# io2db9.net
KiCad netlist of a schematic drawn in EAGLE
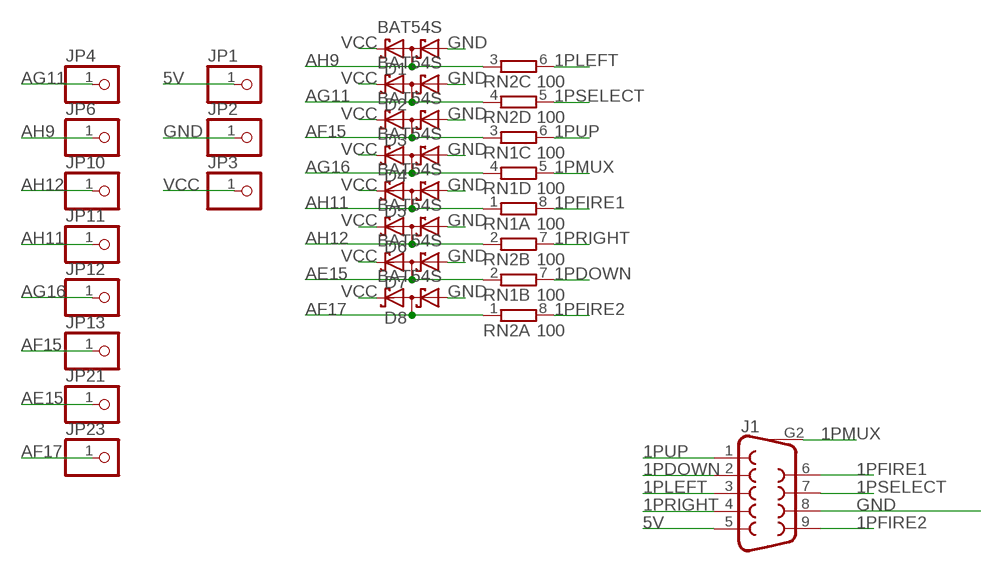
[diagram p0: schematic, sheet 1]

(export (version "E")
  (design (tool "Eeschema 10.0.6"))
  (components
    (comp (ref "D1")
      (value "BAT54S")
      (footprint "eagle-import:SOT23")
      (libsource (lib "eagle-import") (part "BAT54S"))
    )
    (comp (ref "D2")
      (value "BAT54S")
      (footprint "eagle-import:SOT23")
      (libsource (lib "eagle-import") (part "BAT54S"))
    )
    (comp (ref "D3")
      (value "BAT54S")
      (footprint "eagle-import:SOT23")
      (libsource (lib "eagle-import") (part "BAT54S"))
    )
    (comp (ref "D4")
      (value "BAT54S")
      (footprint "eagle-import:SOT23")
      (libsource (lib "eagle-import") (part "BAT54S"))
    )
    (comp (ref "D5")
      (value "BAT54S")
      (footprint "eagle-import:SOT23")
      (libsource (lib "eagle-import") (part "BAT54S"))
    )
    (comp (ref "D6")
      (value "BAT54S")
      (footprint "eagle-import:SOT23")
      (libsource (lib "eagle-import") (part "BAT54S"))
    )
    (comp (ref "D7")
      (value "BAT54S")
      (footprint "eagle-import:SOT23")
      (libsource (lib "eagle-import") (part "BAT54S"))
    )
    (comp (ref "D8")
      (value "BAT54S")
      (footprint "eagle-import:SOT23")
      (libsource (lib "eagle-import") (part "BAT54S"))
    )
    (comp (ref "J1")
      (value "SPARKFUN-CONNECTORS_DB9MALE")
      (footprint "eagle-import:SPARKFUN-CONNECTORS_DB9_MALE")
      (libsource (lib "eagle-import") (part "SPARKFUN-CONNECTORS_DB9MALE"))
    )
    (comp (ref "JP1")
      (value "PINHD-1X1")
      (footprint "eagle-import:1X01")
      (libsource (lib "eagle-import") (part "PINHD-1X1"))
    )
    (comp (ref "JP2")
      (value "PINHD-1X1")
      (footprint "eagle-import:1X01")
      (libsource (lib "eagle-import") (part "PINHD-1X1"))
    )
    (comp (ref "JP3")
      (value "PINHD-1X1")
      (footprint "eagle-import:1X01")
      (libsource (lib "eagle-import") (part "PINHD-1X1"))
    )
    (comp (ref "JP4")
      (value "PINHD-1X1")
      (footprint "eagle-import:1X01")
      (libsource (lib "eagle-import") (part "PINHD-1X1"))
    )
    (comp (ref "JP6")
      (value "PINHD-1X1")
      (footprint "eagle-import:1X01")
      (libsource (lib "eagle-import") (part "PINHD-1X1"))
    )
    (comp (ref "JP10")
      (value "PINHD-1X1")
      (footprint "eagle-import:1X01")
      (libsource (lib "eagle-import") (part "PINHD-1X1"))
    )
    (comp (ref "JP11")
      (value "PINHD-1X1")
      (footprint "eagle-import:1X01")
      (libsource (lib "eagle-import") (part "PINHD-1X1"))
    )
    (comp (ref "JP12")
      (value "PINHD-1X1")
      (footprint "eagle-import:1X01")
      (libsource (lib "eagle-import") (part "PINHD-1X1"))
    )
    (comp (ref "JP13")
      (value "PINHD-1X1")
      (footprint "eagle-import:1X01")
      (libsource (lib "eagle-import") (part "PINHD-1X1"))
    )
    (comp (ref "JP21")
      (value "PINHD-1X1")
      (footprint "eagle-import:1X01")
      (libsource (lib "eagle-import") (part "PINHD-1X1"))
    )
    (comp (ref "JP23")
      (value "PINHD-1X1")
      (footprint "eagle-import:1X01")
      (libsource (lib "eagle-import") (part "PINHD-1X1"))
    )
    (comp (ref "RN1")
      (value "100")
      (footprint "eagle-import:0603-ARC")
      (libsource (lib "eagle-import") (part "4R-N0603-ARC"))
    )
    (comp (ref "RN2")
      (value "100")
      (footprint "eagle-import:0603-ARC")
      (libsource (lib "eagle-import") (part "4R-N0603-ARC"))
    )
  )
  (nets
    (net (code "1") (name "/1PDOWN") (class "Default")
      (node (ref "J1") (pin "2") (pinfunction "2_2") (pintype "passive"))
      (node (ref "RN1") (pin "7") (pinfunction "2_7") (pintype "passive"))
    )
    (net (code "2") (name "/1PFIRE1") (class "Default")
      (node (ref "J1") (pin "6") (pinfunction "6_6") (pintype "passive"))
      (node (ref "RN1") (pin "8") (pinfunction "2_8") (pintype "passive"))
    )
    (net (code "3") (name "/1PFIRE2") (class "Default")
      (node (ref "J1") (pin "9") (pinfunction "9_9") (pintype "passive"))
      (node (ref "RN2") (pin "8") (pinfunction "2_8") (pintype "passive"))
    )
    (net (code "4") (name "/1PLEFT") (class "Default")
      (node (ref "J1") (pin "3") (pinfunction "3_3") (pintype "passive"))
      (node (ref "RN2") (pin "6") (pinfunction "2_6") (pintype "passive"))
    )
    (net (code "5") (name "/1PMUX") (class "Default")
      (node (ref "J1") (pin "G2") (pinfunction "10_G2") (pintype "passive"))
      (node (ref "RN1") (pin "5") (pinfunction "2_5") (pintype "passive"))
    )
    (net (code "6") (name "/1PRIGHT") (class "Default")
      (node (ref "J1") (pin "4") (pinfunction "4_4") (pintype "passive"))
      (node (ref "RN2") (pin "7") (pinfunction "2_7") (pintype "passive"))
    )
    (net (code "7") (name "/1PSELECT") (class "Default")
      (node (ref "J1") (pin "7") (pinfunction "7_7") (pintype "passive"))
      (node (ref "RN2") (pin "5") (pinfunction "2_5") (pintype "passive"))
    )
    (net (code "8") (name "/1PUP") (class "Default")
      (node (ref "J1") (pin "1") (pinfunction "1_1") (pintype "passive"))
      (node (ref "RN1") (pin "6") (pinfunction "2_6") (pintype "passive"))
    )
    (net (code "9") (name "/5V") (class "Default")
      (node (ref "J1") (pin "5") (pinfunction "5_5") (pintype "passive"))
      (node (ref "JP1") (pin "1") (pinfunction "1_1") (pintype "passive"))
    )
    (net (code "10") (name "/AE15") (class "Default")
      (node (ref "D7") (pin "3") (pinfunction "C1A2_3") (pintype "passive"))
      (node (ref "JP21") (pin "1") (pinfunction "1_1") (pintype "passive"))
      (node (ref "RN1") (pin "2") (pinfunction "1_2") (pintype "passive"))
    )
    (net (code "11") (name "/AF15") (class "Default")
      (node (ref "D3") (pin "3") (pinfunction "C1A2_3") (pintype "passive"))
      (node (ref "JP13") (pin "1") (pinfunction "1_1") (pintype "passive"))
      (node (ref "RN1") (pin "3") (pinfunction "1_3") (pintype "passive"))
    )
    (net (code "12") (name "/AF17") (class "Default")
      (node (ref "D8") (pin "3") (pinfunction "C1A2_3") (pintype "passive"))
      (node (ref "JP23") (pin "1") (pinfunction "1_1") (pintype "passive"))
      (node (ref "RN2") (pin "1") (pinfunction "1_1") (pintype "passive"))
    )
    (net (code "13") (name "/AG11") (class "Default")
      (node (ref "D2") (pin "3") (pinfunction "C1A2_3") (pintype "passive"))
      (node (ref "JP4") (pin "1") (pinfunction "1_1") (pintype "passive"))
      (node (ref "RN2") (pin "4") (pinfunction "1_4") (pintype "passive"))
    )
    (net (code "14") (name "/AG16") (class "Default")
      (node (ref "D4") (pin "3") (pinfunction "C1A2_3") (pintype "passive"))
      (node (ref "JP12") (pin "1") (pinfunction "1_1") (pintype "passive"))
      (node (ref "RN1") (pin "4") (pinfunction "1_4") (pintype "passive"))
    )
    (net (code "15") (name "/AH9") (class "Default")
      (node (ref "D1") (pin "3") (pinfunction "C1A2_3") (pintype "passive"))
      (node (ref "JP6") (pin "1") (pinfunction "1_1") (pintype "passive"))
      (node (ref "RN2") (pin "3") (pinfunction "1_3") (pintype "passive"))
    )
    (net (code "16") (name "/AH11") (class "Default")
      (node (ref "D5") (pin "3") (pinfunction "C1A2_3") (pintype "passive"))
      (node (ref "JP11") (pin "1") (pinfunction "1_1") (pintype "passive"))
      (node (ref "RN1") (pin "1") (pinfunction "1_1") (pintype "passive"))
    )
    (net (code "17") (name "/AH12") (class "Default")
      (node (ref "D6") (pin "3") (pinfunction "C1A2_3") (pintype "passive"))
      (node (ref "JP10") (pin "1") (pinfunction "1_1") (pintype "passive"))
      (node (ref "RN2") (pin "2") (pinfunction "1_2") (pintype "passive"))
    )
    (net (code "18") (name "/GND") (class "Default")
      (node (ref "D1") (pin "1") (pinfunction "A1_1") (pintype "passive"))
      (node (ref "D2") (pin "1") (pinfunction "A1_1") (pintype "passive"))
      (node (ref "D3") (pin "1") (pinfunction "A1_1") (pintype "passive"))
      (node (ref "D4") (pin "1") (pinfunction "A1_1") (pintype "passive"))
      (node (ref "D5") (pin "1") (pinfunction "A1_1") (pintype "passive"))
      (node (ref "D6") (pin "1") (pinfunction "A1_1") (pintype "passive"))
      (node (ref "D7") (pin "1") (pinfunction "A1_1") (pintype "passive"))
      (node (ref "D8") (pin "1") (pinfunction "A1_1") (pintype "passive"))
      (node (ref "J1") (pin "8") (pinfunction "8_8") (pintype "passive"))
      (node (ref "JP2") (pin "1") (pinfunction "1_1") (pintype "passive"))
    )
    (net (code "19") (name "/VCC") (class "Default")
      (node (ref "D1") (pin "2") (pinfunction "C2_2") (pintype "passive"))
      (node (ref "D2") (pin "2") (pinfunction "C2_2") (pintype "passive"))
      (node (ref "D3") (pin "2") (pinfunction "C2_2") (pintype "passive"))
      (node (ref "D4") (pin "2") (pinfunction "C2_2") (pintype "passive"))
      (node (ref "D5") (pin "2") (pinfunction "C2_2") (pintype "passive"))
      (node (ref "D6") (pin "2") (pinfunction "C2_2") (pintype "passive"))
      (node (ref "D7") (pin "2") (pinfunction "C2_2") (pintype "passive"))
      (node (ref "D8") (pin "2") (pinfunction "C2_2") (pintype "passive"))
      (node (ref "JP3") (pin "1") (pinfunction "1_1") (pintype "passive"))
    )
  )
)
